# EndStops.net
KiCad netlist of a schematic drawn in Altium Designer
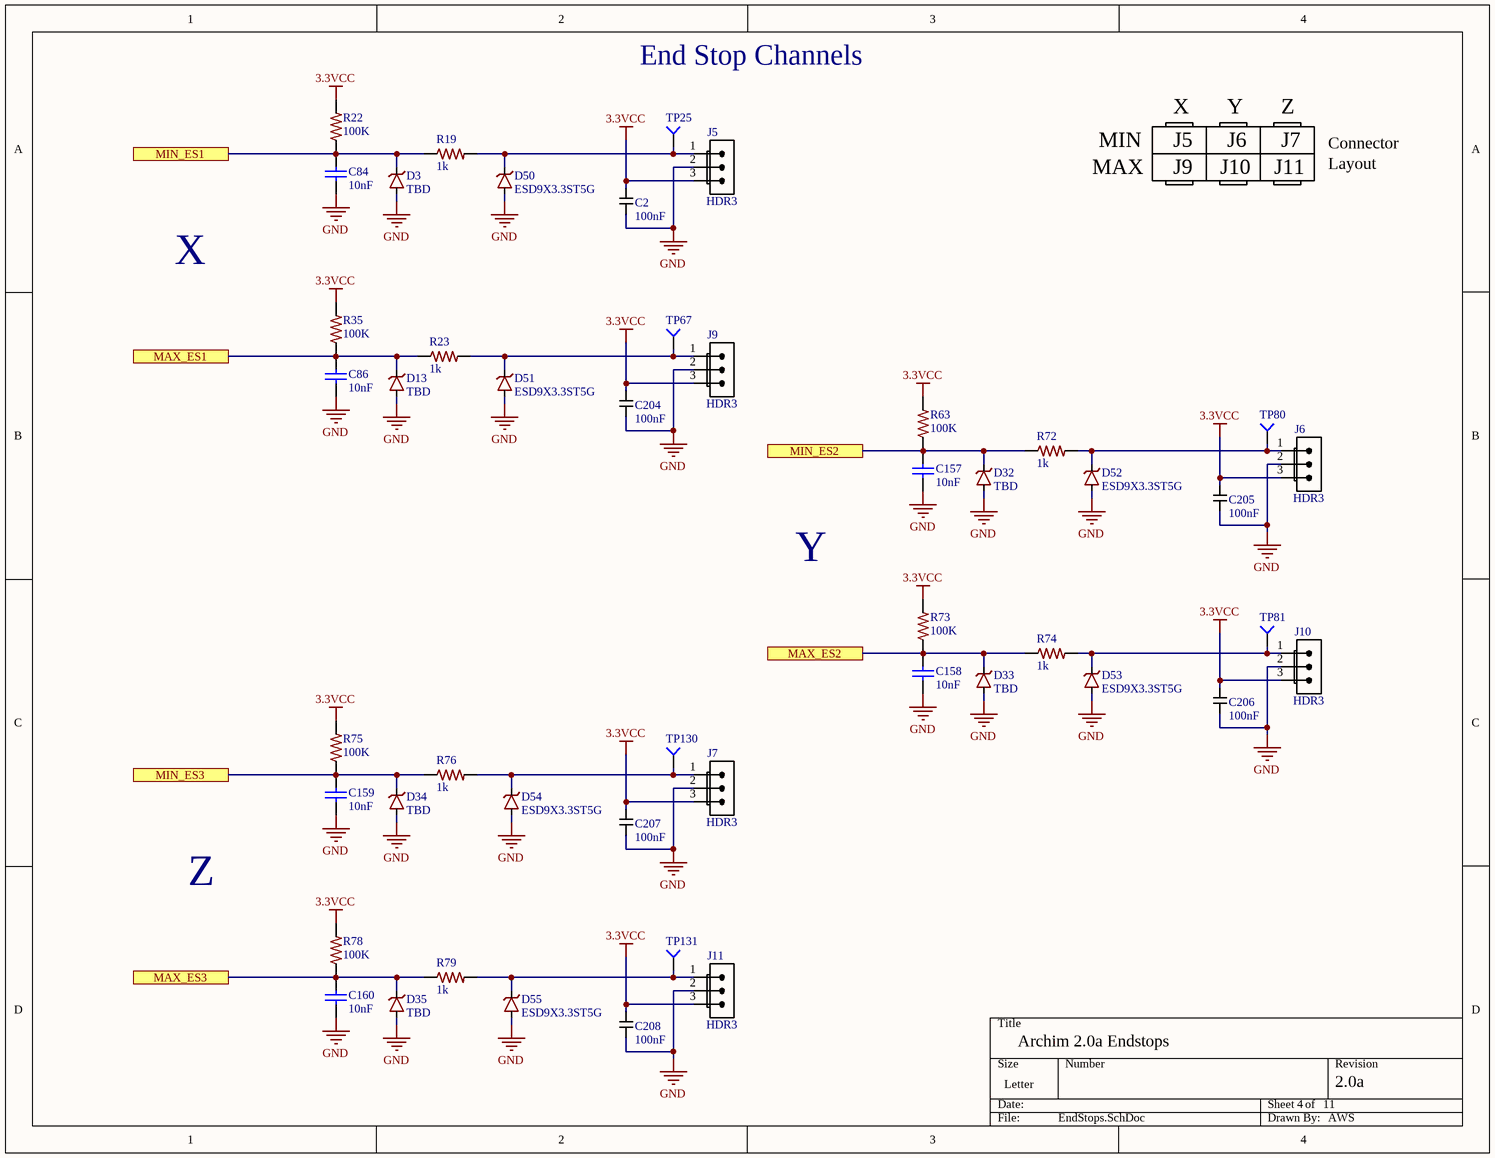
[diagram p0: EndStops.SchDoc]

(export (version "E")
  (design (tool "Eeschema 10.0.6"))
  (components
    (comp (ref "C2")
      (value "100nF")
      (footprint "C0201 Large Pads")
      (description "CAP CER 0.1UF 6.3V 10% X5R 0201")
      (fields (field (name "PART") ".1uF") (field (name "MANUFACTURER") "Samsung"))
      (libsource (lib "Capacitors") (part "100nF 6.3V X5R 0201"))
    )
    (comp (ref "C84")
      (value "10nF")
      (footprint "C0402")
      (description "CAP CER 10nF 50V X7R 0402")
      (fields (field (name "TOLERANCE") "5%") (field (name "MANUFACTURER") "Murata"))
      (libsource (lib "Tigershark3D") (part "GRM155R71H103JA88D"))
    )
    (comp (ref "C86")
      (value "10nF")
      (footprint "C0402")
      (description "CAP CER 10nF 50V X7R 0402")
      (fields (field (name "TOLERANCE") "5%") (field (name "MANUFACTURER") "Murata"))
      (libsource (lib "Tigershark3D") (part "GRM155R71H103JA88D"))
    )
    (comp (ref "C157")
      (value "10nF")
      (footprint "C0402")
      (description "CAP CER 10nF 50V X7R 0402")
      (fields (field (name "TOLERANCE") "5%") (field (name "MANUFACTURER") "Murata"))
      (libsource (lib "Tigershark3D") (part "GRM155R71H103JA88D"))
    )
    (comp (ref "C158")
      (value "10nF")
      (footprint "C0402")
      (description "CAP CER 10nF 50V X7R 0402")
      (fields (field (name "TOLERANCE") "5%") (field (name "MANUFACTURER") "Murata"))
      (libsource (lib "Tigershark3D") (part "GRM155R71H103JA88D"))
    )
    (comp (ref "C159")
      (value "10nF")
      (footprint "C0402")
      (description "CAP CER 10nF 50V X7R 0402")
      (fields (field (name "TOLERANCE") "5%") (field (name "MANUFACTURER") "Murata"))
      (libsource (lib "Tigershark3D") (part "GRM155R71H103JA88D"))
    )
    (comp (ref "C160")
      (value "10nF")
      (footprint "C0402")
      (description "CAP CER 10nF 50V X7R 0402")
      (fields (field (name "TOLERANCE") "5%") (field (name "MANUFACTURER") "Murata"))
      (libsource (lib "Tigershark3D") (part "GRM155R71H103JA88D"))
    )
    (comp (ref "C204")
      (value "100nF")
      (footprint "C0201 Large Pads")
      (description "CAP CER 0.1UF 6.3V 10% X5R 0201")
      (fields (field (name "PART") ".1uF") (field (name "MANUFACTURER") "Samsung"))
      (libsource (lib "Capacitors") (part "100nF 6.3V X5R 0201"))
    )
    (comp (ref "C205")
      (value "100nF")
      (footprint "C0201 Large Pads")
      (description "CAP CER 0.1UF 6.3V 10% X5R 0201")
      (fields (field (name "PART") ".1uF") (field (name "MANUFACTURER") "Samsung"))
      (libsource (lib "Capacitors") (part "100nF 6.3V X5R 0201"))
    )
    (comp (ref "C206")
      (value "100nF")
      (footprint "C0201 Large Pads")
      (description "CAP CER 0.1UF 6.3V 10% X5R 0201")
      (fields (field (name "PART") ".1uF") (field (name "MANUFACTURER") "Samsung"))
      (libsource (lib "Capacitors") (part "100nF 6.3V X5R 0201"))
    )
    (comp (ref "C207")
      (value "100nF")
      (footprint "C0201 Large Pads")
      (description "CAP CER 0.1UF 6.3V 10% X5R 0201")
      (fields (field (name "PART") ".1uF") (field (name "MANUFACTURER") "Samsung"))
      (libsource (lib "Capacitors") (part "100nF 6.3V X5R 0201"))
    )
    (comp (ref "C208")
      (value "100nF")
      (footprint "C0201 Large Pads")
      (description "CAP CER 0.1UF 6.3V 10% X5R 0201")
      (fields (field (name "PART") ".1uF") (field (name "MANUFACTURER") "Samsung"))
      (libsource (lib "Capacitors") (part "100nF 6.3V X5R 0201"))
    )
    (comp (ref "D3") (value "TBD") (footprint "SOD923-D") (libsource (lib "Diodes") (part "SOD923_TBD")))
    (comp (ref "D13") (value "TBD") (footprint "SOD923-D") (libsource (lib "Diodes") (part "SOD923_TBD")))
    (comp (ref "D32") (value "TBD") (footprint "SOD923-D") (libsource (lib "Diodes") (part "SOD923_TBD")))
    (comp (ref "D33") (value "TBD") (footprint "SOD923-D") (libsource (lib "Diodes") (part "SOD923_TBD")))
    (comp (ref "D34") (value "TBD") (footprint "SOD923-D") (libsource (lib "Diodes") (part "SOD923_TBD")))
    (comp (ref "D35") (value "TBD") (footprint "SOD923-D") (libsource (lib "Diodes") (part "SOD923_TBD")))
    (comp (ref "D50")
      (value "ESD9X3.3ST5G")
      (footprint "SOD923-D")
      (description "TVS DIODE 3.3VWM 10.4VC SOD923")
      (fields (field (name "MANUFACTURER") "On Semi") (field (name "TOLERANCE") "-NA-"))
      (libsource (lib "Diodes") (part "ESD9X3.3ST5G"))
    )
    (comp (ref "D51")
      (value "ESD9X3.3ST5G")
      (footprint "SOD923-D")
      (description "TVS DIODE 3.3VWM 10.4VC SOD923")
      (fields (field (name "MANUFACTURER") "On Semi") (field (name "TOLERANCE") "-NA-"))
      (libsource (lib "Diodes") (part "ESD9X3.3ST5G"))
    )
    (comp (ref "D52")
      (value "ESD9X3.3ST5G")
      (footprint "SOD923-D")
      (description "TVS DIODE 3.3VWM 10.4VC SOD923")
      (fields (field (name "MANUFACTURER") "On Semi") (field (name "TOLERANCE") "-NA-"))
      (libsource (lib "Diodes") (part "ESD9X3.3ST5G"))
    )
    (comp (ref "D53")
      (value "ESD9X3.3ST5G")
      (footprint "SOD923-D")
      (description "TVS DIODE 3.3VWM 10.4VC SOD923")
      (fields (field (name "MANUFACTURER") "On Semi") (field (name "TOLERANCE") "-NA-"))
      (libsource (lib "Diodes") (part "ESD9X3.3ST5G"))
    )
    (comp (ref "D54")
      (value "ESD9X3.3ST5G")
      (footprint "SOD923-D")
      (description "TVS DIODE 3.3VWM 10.4VC SOD923")
      (fields (field (name "MANUFACTURER") "On Semi") (field (name "TOLERANCE") "-NA-"))
      (libsource (lib "Diodes") (part "ESD9X3.3ST5G"))
    )
    (comp (ref "D55")
      (value "ESD9X3.3ST5G")
      (footprint "SOD923-D")
      (description "TVS DIODE 3.3VWM 10.4VC SOD923")
      (fields (field (name "MANUFACTURER") "On Semi") (field (name "TOLERANCE") "-NA-"))
      (libsource (lib "Diodes") (part "ESD9X3.3ST5G"))
    )
    (comp (ref "J5")
      (value "HDR3")
      (footprint "70543-02 PIN-IN-PASTE")
      (description "3 Positions Header, Shrouded Connector 0.100\" (2.54mm) Through Hole Gold - Pin in Paste")
      (fields (field (name "MANUFACTURER") "Molex") (field (name "PART") "3 Pin Conn VERT"))
      (libsource (lib "Connectors") (part "CONN 3POS VERT 0.1{dblquote} SHRD LOCKING PIP"))
    )
    (comp (ref "J6")
      (value "HDR3")
      (footprint "70543-02 PIN-IN-PASTE")
      (description "3 Positions Header, Shrouded Connector 0.100\" (2.54mm) Through Hole Gold - Pin in Paste")
      (fields (field (name "MANUFACTURER") "Molex") (field (name "PART") "3 Pin Conn VERT"))
      (libsource (lib "Connectors") (part "CONN 3POS VERT 0.1{dblquote} SHRD LOCKING PIP"))
    )
    (comp (ref "J7")
      (value "HDR3")
      (footprint "70543-02 PIN-IN-PASTE")
      (description "3 Positions Header, Shrouded Connector 0.100\" (2.54mm) Through Hole Gold - Pin in Paste")
      (fields (field (name "MANUFACTURER") "Molex") (field (name "PART") "3 Pin Conn VERT"))
      (libsource (lib "Connectors") (part "CONN 3POS VERT 0.1{dblquote} SHRD LOCKING PIP"))
    )
    (comp (ref "J9")
      (value "HDR3")
      (footprint "70543-02 PIN-IN-PASTE")
      (description "3 Positions Header, Shrouded Connector 0.100\" (2.54mm) Through Hole Gold - Pin in Paste")
      (fields (field (name "MANUFACTURER") "Molex") (field (name "PART") "3 Pin Conn VERT"))
      (libsource (lib "Connectors") (part "CONN 3POS VERT 0.1{dblquote} SHRD LOCKING PIP"))
    )
    (comp (ref "J10")
      (value "HDR3")
      (footprint "70543-02 PIN-IN-PASTE")
      (description "3 Positions Header, Shrouded Connector 0.100\" (2.54mm) Through Hole Gold - Pin in Paste")
      (fields (field (name "MANUFACTURER") "Molex") (field (name "PART") "3 Pin Conn VERT"))
      (libsource (lib "Connectors") (part "CONN 3POS VERT 0.1{dblquote} SHRD LOCKING PIP"))
    )
    (comp (ref "J11")
      (value "HDR3")
      (footprint "70543-02 PIN-IN-PASTE")
      (description "3 Positions Header, Shrouded Connector 0.100\" (2.54mm) Through Hole Gold - Pin in Paste")
      (fields (field (name "MANUFACTURER") "Molex") (field (name "PART") "3 Pin Conn VERT"))
      (libsource (lib "Connectors") (part "CONN 3POS VERT 0.1{dblquote} SHRD LOCKING PIP"))
    )
    (comp (ref "R19")
      (value "1k")
      (footprint "R0402")
      (description "RES 0402 1k 63mW 1%")
      (fields (field (name "MANUFACTURER") "Yageo") (field (name "PART") "1k 1% 0402"))
      (libsource (lib "3Delight") (part "RK73H1ETTP1001F"))
    )
    (comp (ref "R22")
      (value "100K")
      (footprint "R0402")
      (description "RES SMD 100K OHM 1% 1/16W 0402")
      (fields (field (name "MANUFACTURER") "Samsung") (field (name "PART") "100k 1% 0402"))
      (libsource (lib "Tigershark3D") (part "RC1005F104CS"))
    )
    (comp (ref "R23")
      (value "1k")
      (footprint "R0402")
      (description "RES 0402 1k 63mW 1%")
      (fields (field (name "MANUFACTURER") "Yageo") (field (name "PART") "1k 1% 0402"))
      (libsource (lib "3Delight") (part "RK73H1ETTP1001F"))
    )
    (comp (ref "R35")
      (value "100K")
      (footprint "R0402")
      (description "RES SMD 100K OHM 1% 1/16W 0402")
      (fields (field (name "MANUFACTURER") "Samsung") (field (name "PART") "100k 1% 0402"))
      (libsource (lib "Tigershark3D") (part "RC1005F104CS"))
    )
    (comp (ref "R63")
      (value "100K")
      (footprint "R0402")
      (description "RES SMD 100K OHM 1% 1/16W 0402")
      (fields (field (name "MANUFACTURER") "Samsung") (field (name "PART") "100k 1% 0402"))
      (libsource (lib "Tigershark3D") (part "RC1005F104CS"))
    )
    (comp (ref "R72")
      (value "1k")
      (footprint "R0402")
      (description "RES 0402 1k 63mW 1%")
      (fields (field (name "MANUFACTURER") "Yageo") (field (name "PART") "1k 1% 0402"))
      (libsource (lib "3Delight") (part "RK73H1ETTP1001F"))
    )
    (comp (ref "R73")
      (value "100K")
      (footprint "R0402")
      (description "RES SMD 100K OHM 1% 1/16W 0402")
      (fields (field (name "MANUFACTURER") "Samsung") (field (name "PART") "100k 1% 0402"))
      (libsource (lib "Tigershark3D") (part "RC1005F104CS"))
    )
    (comp (ref "R74")
      (value "1k")
      (footprint "R0402")
      (description "RES 0402 1k 63mW 1%")
      (fields (field (name "MANUFACTURER") "Yageo") (field (name "PART") "1k 1% 0402"))
      (libsource (lib "3Delight") (part "RK73H1ETTP1001F"))
    )
    (comp (ref "R75")
      (value "100K")
      (footprint "R0402")
      (description "RES SMD 100K OHM 1% 1/16W 0402")
      (fields (field (name "MANUFACTURER") "Samsung") (field (name "PART") "100k 1% 0402"))
      (libsource (lib "Tigershark3D") (part "RC1005F104CS"))
    )
    (comp (ref "R76")
      (value "1k")
      (footprint "R0402")
      (description "RES 0402 1k 63mW 1%")
      (fields (field (name "MANUFACTURER") "Yageo") (field (name "PART") "1k 1% 0402"))
      (libsource (lib "3Delight") (part "RK73H1ETTP1001F"))
    )
    (comp (ref "R78")
      (value "100K")
      (footprint "R0402")
      (description "RES SMD 100K OHM 1% 1/16W 0402")
      (fields (field (name "MANUFACTURER") "Samsung") (field (name "PART") "100k 1% 0402"))
      (libsource (lib "Tigershark3D") (part "RC1005F104CS"))
    )
    (comp (ref "R79")
      (value "1k")
      (footprint "R0402")
      (description "RES 0402 1k 63mW 1%")
      (fields (field (name "MANUFACTURER") "Yageo") (field (name "PART") "1k 1% 0402"))
      (libsource (lib "3Delight") (part "RK73H1ETTP1001F"))
    )
    (comp (ref "TP25")
      (value "TP4")
      (footprint "TP-2")
      (description "Socket")
      (libsource (lib "Archim") (part "Socket"))
    )
    (comp (ref "TP67")
      (value "TP4")
      (footprint "TP-2")
      (description "Socket")
      (libsource (lib "Archim") (part "Socket"))
    )
    (comp (ref "TP80")
      (value "TP4")
      (footprint "TP-2")
      (description "Socket")
      (libsource (lib "Archim") (part "Socket"))
    )
    (comp (ref "TP81")
      (value "TP4")
      (footprint "TP-2")
      (description "Socket")
      (libsource (lib "Archim") (part "Socket"))
    )
    (comp (ref "TP130")
      (value "TP4")
      (footprint "TP-2")
      (description "Socket")
      (libsource (lib "Archim") (part "Socket"))
    )
    (comp (ref "TP131")
      (value "TP4")
      (footprint "TP-2")
      (description "Socket")
      (libsource (lib "Archim") (part "Socket"))
    )
  )
  (nets
    (net (code "1") (name "/MAX_ES1") (class "Default")
      (node (ref "C86") (pin "1") (pinfunction "1_1") (pintype "passive"))
      (node (ref "D13") (pin "K") (pinfunction "K_K") (pintype "passive"))
      (node (ref "R23") (pin "1") (pinfunction "1_1") (pintype "passive"))
      (node (ref "R35") (pin "1") (pinfunction "1_1") (pintype "passive"))
    )
    (net (code "2") (name "/MAX_ES2") (class "Default")
      (node (ref "C158") (pin "1") (pinfunction "1_1") (pintype "passive"))
      (node (ref "D33") (pin "K") (pinfunction "K_K") (pintype "passive"))
      (node (ref "R73") (pin "1") (pinfunction "1_1") (pintype "passive"))
      (node (ref "R74") (pin "1") (pinfunction "1_1") (pintype "passive"))
    )
    (net (code "3") (name "/MAX_ES3") (class "Default")
      (node (ref "C160") (pin "1") (pinfunction "1_1") (pintype "passive"))
      (node (ref "D35") (pin "K") (pinfunction "K_K") (pintype "passive"))
      (node (ref "R78") (pin "1") (pinfunction "1_1") (pintype "passive"))
      (node (ref "R79") (pin "1") (pinfunction "1_1") (pintype "passive"))
    )
    (net (code "4") (name "/MIN_ES1") (class "Default")
      (node (ref "C84") (pin "1") (pinfunction "1_1") (pintype "passive"))
      (node (ref "D3") (pin "K") (pinfunction "K_K") (pintype "passive"))
      (node (ref "R19") (pin "1") (pinfunction "1_1") (pintype "passive"))
      (node (ref "R22") (pin "1") (pinfunction "1_1") (pintype "passive"))
    )
    (net (code "5") (name "/MIN_ES2") (class "Default")
      (node (ref "C157") (pin "1") (pinfunction "1_1") (pintype "passive"))
      (node (ref "D32") (pin "K") (pinfunction "K_K") (pintype "passive"))
      (node (ref "R63") (pin "1") (pinfunction "1_1") (pintype "passive"))
      (node (ref "R72") (pin "1") (pinfunction "1_1") (pintype "passive"))
    )
    (net (code "6") (name "/MIN_ES3") (class "Default")
      (node (ref "C159") (pin "1") (pinfunction "1_1") (pintype "passive"))
      (node (ref "D34") (pin "K") (pinfunction "K_K") (pintype "passive"))
      (node (ref "R75") (pin "1") (pinfunction "1_1") (pintype "passive"))
      (node (ref "R76") (pin "1") (pinfunction "1_1") (pintype "passive"))
    )
    (net (code "7") (name "3.3VCC") (class "Default")
      (node (ref "C2") (pin "2") (pinfunction "2_2") (pintype "passive"))
      (node (ref "C204") (pin "2") (pinfunction "2_2") (pintype "passive"))
      (node (ref "C205") (pin "2") (pinfunction "2_2") (pintype "passive"))
      (node (ref "C206") (pin "2") (pinfunction "2_2") (pintype "passive"))
      (node (ref "C207") (pin "2") (pinfunction "2_2") (pintype "passive"))
      (node (ref "C208") (pin "2") (pinfunction "2_2") (pintype "passive"))
      (node (ref "J10") (pin "3") (pinfunction "S_3") (pintype "passive"))
      (node (ref "J11") (pin "3") (pinfunction "S_3") (pintype "passive"))
      (node (ref "J5") (pin "3") (pinfunction "S_3") (pintype "passive"))
      (node (ref "J6") (pin "3") (pinfunction "S_3") (pintype "passive"))
      (node (ref "J7") (pin "3") (pinfunction "S_3") (pintype "passive"))
      (node (ref "J9") (pin "3") (pinfunction "S_3") (pintype "passive"))
      (node (ref "R22") (pin "2") (pinfunction "2_2") (pintype "passive"))
      (node (ref "R35") (pin "2") (pinfunction "2_2") (pintype "passive"))
      (node (ref "R63") (pin "2") (pinfunction "2_2") (pintype "passive"))
      (node (ref "R73") (pin "2") (pinfunction "2_2") (pintype "passive"))
      (node (ref "R75") (pin "2") (pinfunction "2_2") (pintype "passive"))
      (node (ref "R78") (pin "2") (pinfunction "2_2") (pintype "passive"))
    )
    (net (code "8") (name "GND") (class "Default")
      (node (ref "C157") (pin "2") (pinfunction "2_2") (pintype "passive"))
      (node (ref "C158") (pin "2") (pinfunction "2_2") (pintype "passive"))
      (node (ref "C159") (pin "2") (pinfunction "2_2") (pintype "passive"))
      (node (ref "C160") (pin "2") (pinfunction "2_2") (pintype "passive"))
      (node (ref "C2") (pin "1") (pinfunction "1_1") (pintype "passive"))
      (node (ref "C204") (pin "1") (pinfunction "1_1") (pintype "passive"))
      (node (ref "C205") (pin "1") (pinfunction "1_1") (pintype "passive"))
      (node (ref "C206") (pin "1") (pinfunction "1_1") (pintype "passive"))
      (node (ref "C207") (pin "1") (pinfunction "1_1") (pintype "passive"))
      (node (ref "C208") (pin "1") (pinfunction "1_1") (pintype "passive"))
      (node (ref "C84") (pin "2") (pinfunction "2_2") (pintype "passive"))
      (node (ref "C86") (pin "2") (pinfunction "2_2") (pintype "passive"))
      (node (ref "D13") (pin "A") (pinfunction "A_A") (pintype "passive"))
      (node (ref "D3") (pin "A") (pinfunction "A_A") (pintype "passive"))
      (node (ref "D32") (pin "A") (pinfunction "A_A") (pintype "passive"))
      (node (ref "D33") (pin "A") (pinfunction "A_A") (pintype "passive"))
      (node (ref "D34") (pin "A") (pinfunction "A_A") (pintype "passive"))
      (node (ref "D35") (pin "A") (pinfunction "A_A") (pintype "passive"))
      (node (ref "D50") (pin "A") (pinfunction "A_A") (pintype "passive"))
      (node (ref "D51") (pin "A") (pinfunction "A_A") (pintype "passive"))
      (node (ref "D52") (pin "A") (pinfunction "A_A") (pintype "passive"))
      (node (ref "D53") (pin "A") (pinfunction "A_A") (pintype "passive"))
      (node (ref "D54") (pin "A") (pinfunction "A_A") (pintype "passive"))
      (node (ref "D55") (pin "A") (pinfunction "A_A") (pintype "passive"))
      (node (ref "J10") (pin "2") (pinfunction "S_2") (pintype "passive"))
      (node (ref "J11") (pin "2") (pinfunction "S_2") (pintype "passive"))
      (node (ref "J5") (pin "2") (pinfunction "S_2") (pintype "passive"))
      (node (ref "J6") (pin "2") (pinfunction "S_2") (pintype "passive"))
      (node (ref "J7") (pin "2") (pinfunction "S_2") (pintype "passive"))
      (node (ref "J9") (pin "2") (pinfunction "S_2") (pintype "passive"))
    )
    (net (code "9") (name "Net-(D50-PadK)") (class "Default")
      (node (ref "D50") (pin "K") (pinfunction "K_K") (pintype "passive"))
      (node (ref "J5") (pin "1") (pinfunction "S_1") (pintype "passive"))
      (node (ref "R19") (pin "2") (pinfunction "2_2") (pintype "passive"))
      (node (ref "TP25") (pin "1") (pinfunction "1_1") (pintype "passive"))
    )
    (net (code "10") (name "Net-(D51-PadK)") (class "Default")
      (node (ref "D51") (pin "K") (pinfunction "K_K") (pintype "passive"))
      (node (ref "J9") (pin "1") (pinfunction "S_1") (pintype "passive"))
      (node (ref "R23") (pin "2") (pinfunction "2_2") (pintype "passive"))
      (node (ref "TP67") (pin "1") (pinfunction "1_1") (pintype "passive"))
    )
    (net (code "11") (name "Net-(D52-PadK)") (class "Default")
      (node (ref "D52") (pin "K") (pinfunction "K_K") (pintype "passive"))
      (node (ref "J6") (pin "1") (pinfunction "S_1") (pintype "passive"))
      (node (ref "R72") (pin "2") (pinfunction "2_2") (pintype "passive"))
      (node (ref "TP80") (pin "1") (pinfunction "1_1") (pintype "passive"))
    )
    (net (code "12") (name "Net-(D53-PadK)") (class "Default")
      (node (ref "D53") (pin "K") (pinfunction "K_K") (pintype "passive"))
      (node (ref "J10") (pin "1") (pinfunction "S_1") (pintype "passive"))
      (node (ref "R74") (pin "2") (pinfunction "2_2") (pintype "passive"))
      (node (ref "TP81") (pin "1") (pinfunction "1_1") (pintype "passive"))
    )
    (net (code "13") (name "Net-(D54-PadK)") (class "Default")
      (node (ref "D54") (pin "K") (pinfunction "K_K") (pintype "passive"))
      (node (ref "J7") (pin "1") (pinfunction "S_1") (pintype "passive"))
      (node (ref "R76") (pin "2") (pinfunction "2_2") (pintype "passive"))
      (node (ref "TP130") (pin "1") (pinfunction "1_1") (pintype "passive"))
    )
    (net (code "14") (name "Net-(D55-PadK)") (class "Default")
      (node (ref "D55") (pin "K") (pinfunction "K_K") (pintype "passive"))
      (node (ref "J11") (pin "1") (pinfunction "S_1") (pintype "passive"))
      (node (ref "R79") (pin "2") (pinfunction "2_2") (pintype "passive"))
      (node (ref "TP131") (pin "1") (pinfunction "1_1") (pintype "passive"))
    )
  )
)
